# Hatch2022Badge0805_2.net
KiCad netlist of a schematic drawn in EAGLE
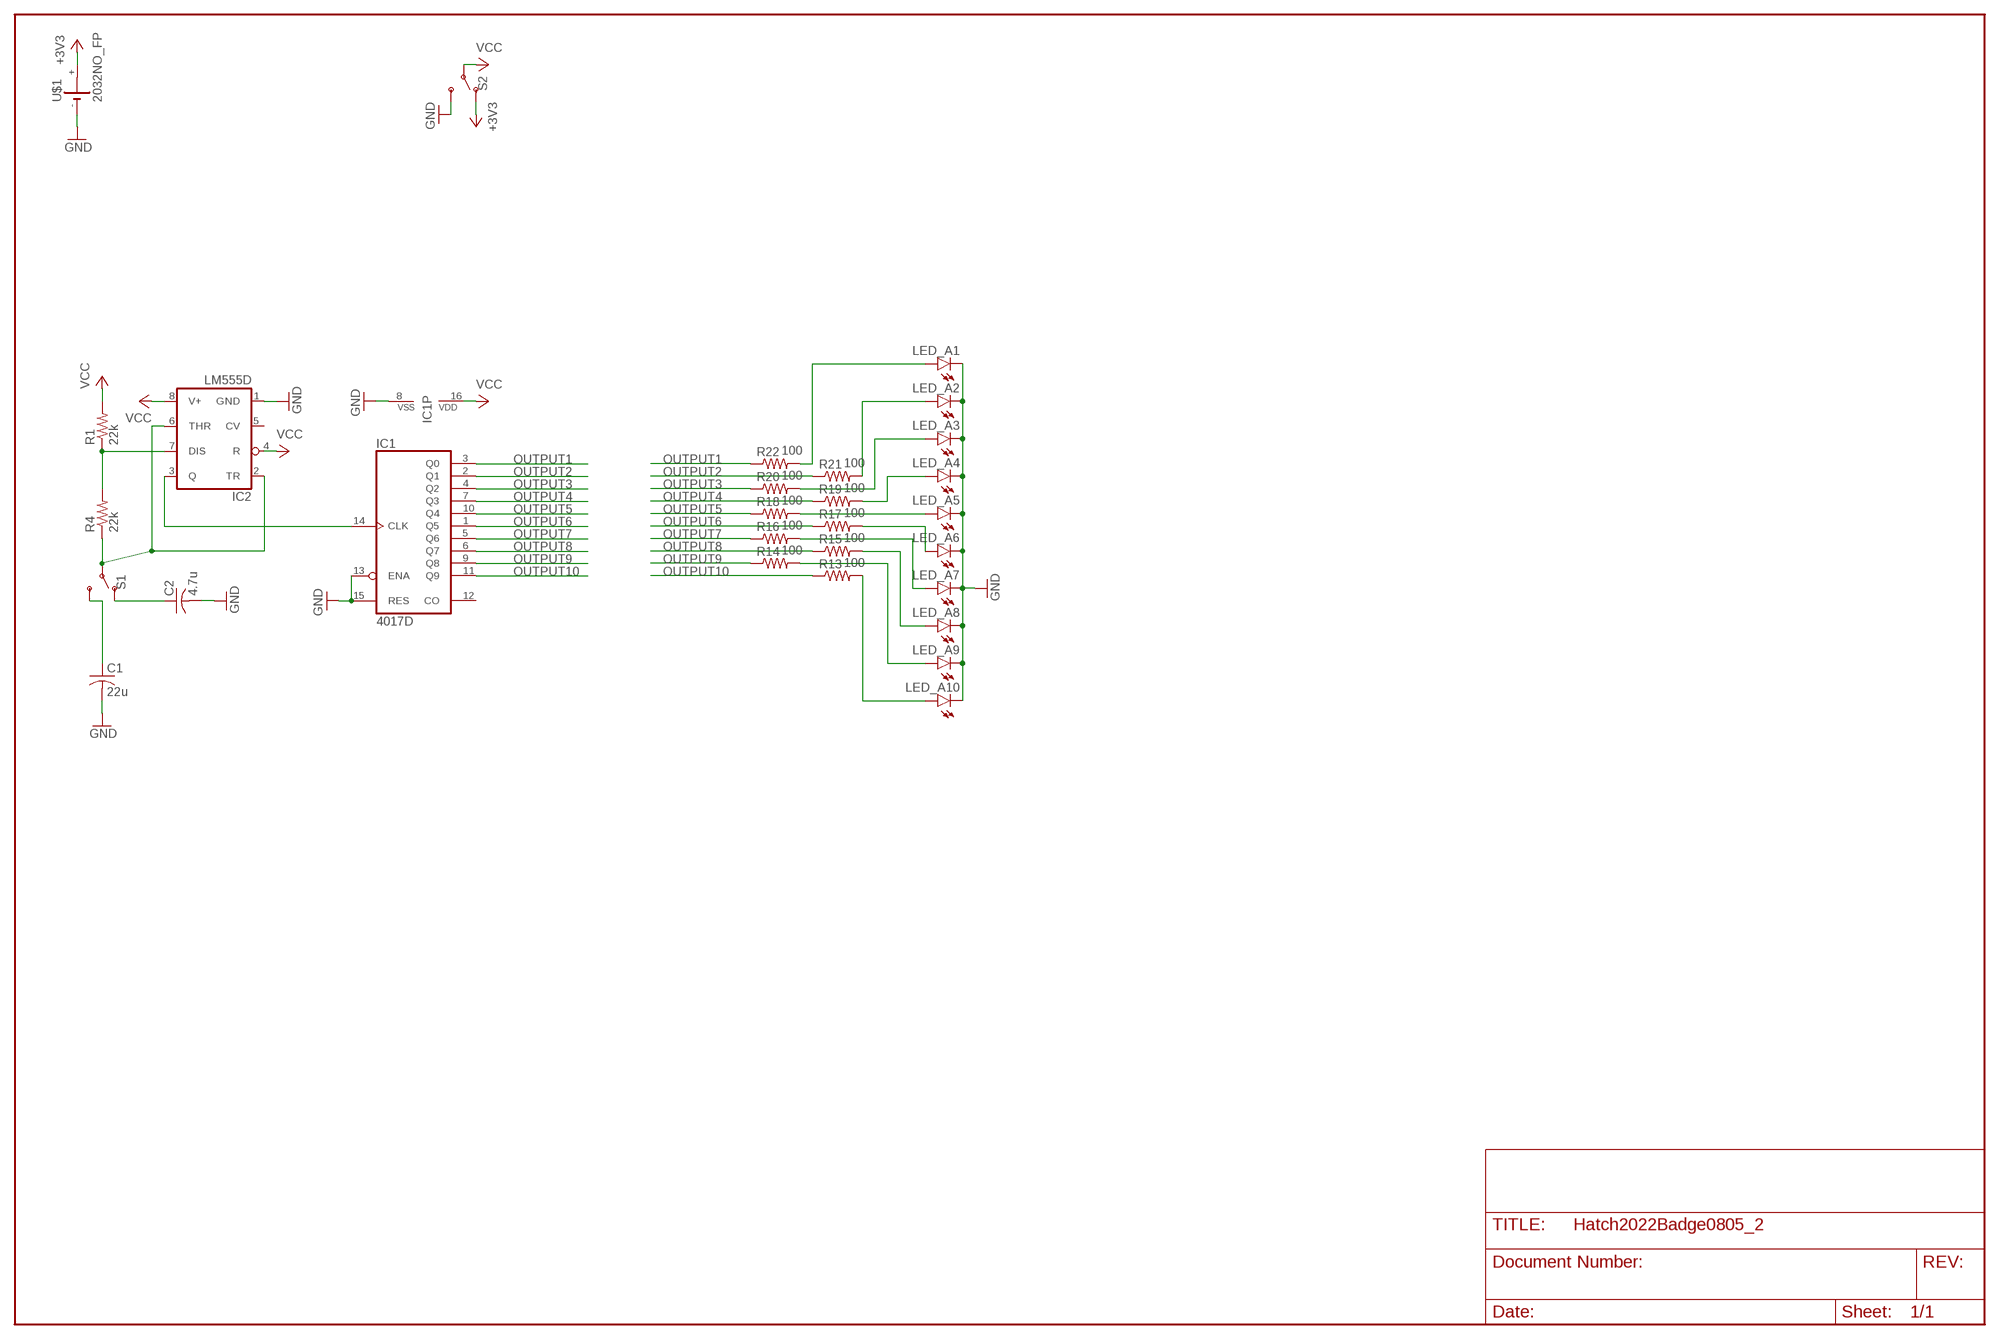
[diagram p0: schematic, sheet 1]

(export (version "E")
  (design (tool "Eeschema 10.0.6"))
  (components
    (comp (ref "C1")
      (value "22u")
      (footprint "eagle-import:C0805")
      (libsource (lib "eagle-import") (part "C-USC0805"))
    )
    (comp (ref "C2")
      (value "4.7u")
      (footprint "eagle-import:C0805")
      (libsource (lib "eagle-import") (part "C-USC0805"))
    )
    (comp (ref "IC1")
      (value "4017D")
      (footprint "eagle-import:SO16")
      (libsource (lib "eagle-import") (part "4017D"))
    )
    (comp (ref "IC2")
      (value "LM555D")
      (footprint "eagle-import:SO08")
      (libsource (lib "eagle-import") (part "555DLM"))
    )
    (comp (ref "LED_A1")
      (value "LEDSML0805")
      (footprint "eagle-import:SML0805")
      (libsource (lib "eagle-import") (part "LEDSML0805"))
    )
    (comp (ref "LED_A2")
      (value "LEDSML0805")
      (footprint "eagle-import:SML0805")
      (libsource (lib "eagle-import") (part "LEDSML0805"))
    )
    (comp (ref "LED_A3")
      (value "LEDSML0805")
      (footprint "eagle-import:SML0805")
      (libsource (lib "eagle-import") (part "LEDSML0805"))
    )
    (comp (ref "LED_A4")
      (value "LEDSML0805")
      (footprint "eagle-import:SML0805")
      (libsource (lib "eagle-import") (part "LEDSML0805"))
    )
    (comp (ref "LED_A5")
      (value "LEDSML0805")
      (footprint "eagle-import:SML0805")
      (libsource (lib "eagle-import") (part "LEDSML0805"))
    )
    (comp (ref "LED_A6")
      (value "LEDSML0805")
      (footprint "eagle-import:SML0805")
      (libsource (lib "eagle-import") (part "LEDSML0805"))
    )
    (comp (ref "LED_A7")
      (value "LEDSML0805")
      (footprint "eagle-import:SML0805")
      (libsource (lib "eagle-import") (part "LEDSML0805"))
    )
    (comp (ref "LED_A8")
      (value "LEDSML0805")
      (footprint "eagle-import:SML0805")
      (libsource (lib "eagle-import") (part "LEDSML0805"))
    )
    (comp (ref "LED_A9")
      (value "LEDSML0805")
      (footprint "eagle-import:SML0805")
      (libsource (lib "eagle-import") (part "LEDSML0805"))
    )
    (comp (ref "LED_A10")
      (value "LEDSML0805")
      (footprint "eagle-import:SML0805")
      (libsource (lib "eagle-import") (part "LEDSML0805"))
    )
    (comp (ref "R1")
      (value "22k")
      (footprint "eagle-import:R0805")
      (libsource (lib "eagle-import") (part "R-US_R0805"))
    )
    (comp (ref "R4")
      (value "22k")
      (footprint "eagle-import:R0805")
      (libsource (lib "eagle-import") (part "R-US_R0805"))
    )
    (comp (ref "R13")
      (value "100")
      (footprint "eagle-import:R0805")
      (libsource (lib "eagle-import") (part "R-US_R0805"))
    )
    (comp (ref "R14")
      (value "100")
      (footprint "eagle-import:R0805")
      (libsource (lib "eagle-import") (part "R-US_R0805"))
    )
    (comp (ref "R15")
      (value "100")
      (footprint "eagle-import:R0805")
      (libsource (lib "eagle-import") (part "R-US_R0805"))
    )
    (comp (ref "R16")
      (value "100")
      (footprint "eagle-import:R0805")
      (libsource (lib "eagle-import") (part "R-US_R0805"))
    )
    (comp (ref "R17")
      (value "100")
      (footprint "eagle-import:R0805")
      (libsource (lib "eagle-import") (part "R-US_R0805"))
    )
    (comp (ref "R18")
      (value "100")
      (footprint "eagle-import:R0805")
      (libsource (lib "eagle-import") (part "R-US_R0805"))
    )
    (comp (ref "R19")
      (value "100")
      (footprint "eagle-import:R0805")
      (libsource (lib "eagle-import") (part "R-US_R0805"))
    )
    (comp (ref "R20")
      (value "100")
      (footprint "eagle-import:R0805")
      (libsource (lib "eagle-import") (part "R-US_R0805"))
    )
    (comp (ref "R21")
      (value "100")
      (footprint "eagle-import:R0805")
      (libsource (lib "eagle-import") (part "R-US_R0805"))
    )
    (comp (ref "R22")
      (value "100")
      (footprint "eagle-import:R0805")
      (libsource (lib "eagle-import") (part "R-US_R0805"))
    )
    (comp (ref "S1")
      (value "SWITCH-SPDT-SMD-AYZ0202")
      (footprint "eagle-import:SWITCH_DPDT_SMD_AYZ0202")
      (libsource (lib "eagle-import") (part "SWITCH-SPDT-SMD-AYZ0202"))
    )
    (comp (ref "S2")
      (value "SWITCH-SPDT-SMD-AYZ0202")
      (footprint "eagle-import:SWITCH_DPDT_SMD_AYZ0202")
      (libsource (lib "eagle-import") (part "SWITCH-SPDT-SMD-AYZ0202"))
    )
    (comp (ref "U$1")
      (value "2032NO_FP")
      (footprint "eagle-import:2032_NO_FP")
      (libsource (lib "eagle-import") (part "2032NO_FP"))
    )
  )
  (nets
    (net (code "1") (name "+3V3") (class "Default")
      (node (ref "S2") (pin "1") (pinfunction "O_1") (pintype "passive"))
      (node (ref "U$1") (pin "+") (pinfunction "+_+") (pintype "passive"))
    )
    (net (code "2") (name "/OUTPUT1") (class "Default")
      (node (ref "IC1") (pin "3") (pinfunction "Q0_3") (pintype "output"))
      (node (ref "R22") (pin "1") (pinfunction "1_1") (pintype "passive"))
    )
    (net (code "3") (name "/OUTPUT2") (class "Default")
      (node (ref "IC1") (pin "2") (pinfunction "Q1_2") (pintype "output"))
      (node (ref "R21") (pin "1") (pinfunction "1_1") (pintype "passive"))
    )
    (net (code "4") (name "/OUTPUT3") (class "Default")
      (node (ref "IC1") (pin "4") (pinfunction "Q2_4") (pintype "output"))
      (node (ref "R20") (pin "1") (pinfunction "1_1") (pintype "passive"))
    )
    (net (code "5") (name "/OUTPUT4") (class "Default")
      (node (ref "IC1") (pin "7") (pinfunction "Q3_7") (pintype "output"))
      (node (ref "R19") (pin "1") (pinfunction "1_1") (pintype "passive"))
    )
    (net (code "6") (name "/OUTPUT5") (class "Default")
      (node (ref "IC1") (pin "10") (pinfunction "Q4_10") (pintype "output"))
      (node (ref "R18") (pin "1") (pinfunction "1_1") (pintype "passive"))
    )
    (net (code "7") (name "/OUTPUT6") (class "Default")
      (node (ref "IC1") (pin "1") (pinfunction "Q5_1") (pintype "output"))
      (node (ref "R17") (pin "1") (pinfunction "1_1") (pintype "passive"))
    )
    (net (code "8") (name "/OUTPUT7") (class "Default")
      (node (ref "IC1") (pin "5") (pinfunction "Q6_5") (pintype "output"))
      (node (ref "R16") (pin "1") (pinfunction "1_1") (pintype "passive"))
    )
    (net (code "9") (name "/OUTPUT8") (class "Default")
      (node (ref "IC1") (pin "6") (pinfunction "Q7_6") (pintype "output"))
      (node (ref "R15") (pin "1") (pinfunction "1_1") (pintype "passive"))
    )
    (net (code "10") (name "/OUTPUT9") (class "Default")
      (node (ref "IC1") (pin "9") (pinfunction "Q8_9") (pintype "output"))
      (node (ref "R14") (pin "1") (pinfunction "1_1") (pintype "passive"))
    )
    (net (code "11") (name "/OUTPUT10") (class "Default")
      (node (ref "IC1") (pin "11") (pinfunction "Q9_11") (pintype "output"))
      (node (ref "R13") (pin "1") (pinfunction "1_1") (pintype "passive"))
    )
    (net (code "12") (name "GND") (class "Default")
      (node (ref "C1") (pin "2") (pinfunction "2_2") (pintype "passive"))
      (node (ref "C2") (pin "2") (pinfunction "2_2") (pintype "passive"))
      (node (ref "IC1") (pin "13") (pinfunction "ENA_13") (pintype "input"))
      (node (ref "IC1") (pin "15") (pinfunction "RES_15") (pintype "input"))
      (node (ref "IC1") (pin "8") (pinfunction "VSS_8") (pintype "power_in"))
      (node (ref "IC2") (pin "1") (pinfunction "GND_1") (pintype "power_in"))
      (node (ref "LED_A1") (pin "C") (pinfunction "C_C") (pintype "passive"))
      (node (ref "LED_A10") (pin "C") (pinfunction "C_C") (pintype "passive"))
      (node (ref "LED_A2") (pin "C") (pinfunction "C_C") (pintype "passive"))
      (node (ref "LED_A3") (pin "C") (pinfunction "C_C") (pintype "passive"))
      (node (ref "LED_A4") (pin "C") (pinfunction "C_C") (pintype "passive"))
      (node (ref "LED_A5") (pin "C") (pinfunction "C_C") (pintype "passive"))
      (node (ref "LED_A6") (pin "C") (pinfunction "C_C") (pintype "passive"))
      (node (ref "LED_A7") (pin "C") (pinfunction "C_C") (pintype "passive"))
      (node (ref "LED_A8") (pin "C") (pinfunction "C_C") (pintype "passive"))
      (node (ref "LED_A9") (pin "C") (pinfunction "C_C") (pintype "passive"))
      (node (ref "S2") (pin "3") (pinfunction "S_3") (pintype "passive"))
      (node (ref "U$1") (pin "-") (pinfunction "-_-") (pintype "passive"))
    )
    (net (code "13") (name "Net-(IC1A-CLK)") (class "Default")
      (node (ref "IC1") (pin "14") (pinfunction "CLK_14") (pintype "input"))
      (node (ref "IC2") (pin "3") (pinfunction "Q_3") (pintype "output"))
    )
    (net (code "14") (name "Net-(IC2-DIS)") (class "Default")
      (node (ref "IC2") (pin "7") (pinfunction "DIS_7") (pintype "input"))
      (node (ref "R1") (pin "1") (pinfunction "1_1") (pintype "passive"))
      (node (ref "R4") (pin "2") (pinfunction "2_2") (pintype "passive"))
    )
    (net (code "15") (name "Net-(IC2-THR)") (class "Default")
      (node (ref "IC2") (pin "2") (pinfunction "TR_2") (pintype "input"))
      (node (ref "IC2") (pin "6") (pinfunction "THR_6") (pintype "input"))
      (node (ref "R4") (pin "1") (pinfunction "1_1") (pintype "passive"))
      (node (ref "S1") (pin "2") (pinfunction "P_2") (pintype "passive"))
    )
    (net (code "16") (name "Net-(LED_A1-PadA)") (class "Default")
      (node (ref "LED_A1") (pin "A") (pinfunction "A_A") (pintype "passive"))
      (node (ref "R22") (pin "2") (pinfunction "2_2") (pintype "passive"))
    )
    (net (code "17") (name "Net-(LED_A2-PadA)") (class "Default")
      (node (ref "LED_A2") (pin "A") (pinfunction "A_A") (pintype "passive"))
      (node (ref "R21") (pin "2") (pinfunction "2_2") (pintype "passive"))
    )
    (net (code "18") (name "Net-(LED_A3-PadA)") (class "Default")
      (node (ref "LED_A3") (pin "A") (pinfunction "A_A") (pintype "passive"))
      (node (ref "R20") (pin "2") (pinfunction "2_2") (pintype "passive"))
    )
    (net (code "19") (name "Net-(LED_A4-PadA)") (class "Default")
      (node (ref "LED_A4") (pin "A") (pinfunction "A_A") (pintype "passive"))
      (node (ref "R19") (pin "2") (pinfunction "2_2") (pintype "passive"))
    )
    (net (code "20") (name "Net-(LED_A5-PadA)") (class "Default")
      (node (ref "LED_A5") (pin "A") (pinfunction "A_A") (pintype "passive"))
      (node (ref "R18") (pin "2") (pinfunction "2_2") (pintype "passive"))
    )
    (net (code "21") (name "Net-(LED_A6-PadA)") (class "Default")
      (node (ref "LED_A6") (pin "A") (pinfunction "A_A") (pintype "passive"))
      (node (ref "R17") (pin "2") (pinfunction "2_2") (pintype "passive"))
    )
    (net (code "22") (name "Net-(LED_A7-PadA)") (class "Default")
      (node (ref "LED_A7") (pin "A") (pinfunction "A_A") (pintype "passive"))
      (node (ref "R16") (pin "2") (pinfunction "2_2") (pintype "passive"))
    )
    (net (code "23") (name "Net-(LED_A8-PadA)") (class "Default")
      (node (ref "LED_A8") (pin "A") (pinfunction "A_A") (pintype "passive"))
      (node (ref "R15") (pin "2") (pinfunction "2_2") (pintype "passive"))
    )
    (net (code "24") (name "Net-(LED_A9-PadA)") (class "Default")
      (node (ref "LED_A9") (pin "A") (pinfunction "A_A") (pintype "passive"))
      (node (ref "R14") (pin "2") (pinfunction "2_2") (pintype "passive"))
    )
    (net (code "25") (name "Net-(LED_A10-PadA)") (class "Default")
      (node (ref "LED_A10") (pin "A") (pinfunction "A_A") (pintype "passive"))
      (node (ref "R13") (pin "2") (pinfunction "2_2") (pintype "passive"))
    )
    (net (code "26") (name "Net-(S1-O)") (class "Default")
      (node (ref "C2") (pin "1") (pinfunction "1_1") (pintype "passive"))
      (node (ref "S1") (pin "1") (pinfunction "O_1") (pintype "passive"))
    )
    (net (code "27") (name "Net-(S1-S)") (class "Default")
      (node (ref "C1") (pin "1") (pinfunction "1_1") (pintype "passive"))
      (node (ref "S1") (pin "3") (pinfunction "S_3") (pintype "passive"))
    )
    (net (code "28") (name "VCC") (class "Default")
      (node (ref "IC1") (pin "16") (pinfunction "VDD_16") (pintype "power_in"))
      (node (ref "IC2") (pin "4") (pinfunction "R_4") (pintype "input"))
      (node (ref "IC2") (pin "8") (pinfunction "V+_8") (pintype "power_in"))
      (node (ref "R1") (pin "2") (pinfunction "2_2") (pintype "passive"))
      (node (ref "S2") (pin "2") (pinfunction "P_2") (pintype "passive"))
    )
    (net (code "29") (name "unconnected-(IC1A-CO-Pad12)") (class "Default")
      (node (ref "IC1") (pin "12") (pinfunction "CO_12") (pintype "output"))
    )
    (net (code "30") (name "unconnected-(IC2-CV-Pad5)") (class "Default")
      (node (ref "IC2") (pin "5") (pinfunction "CV_5") (pintype "input"))
    )
  )
)
